# 12_-MCU_INPUTS.net
KiCad netlist of a schematic drawn in Altium Designer
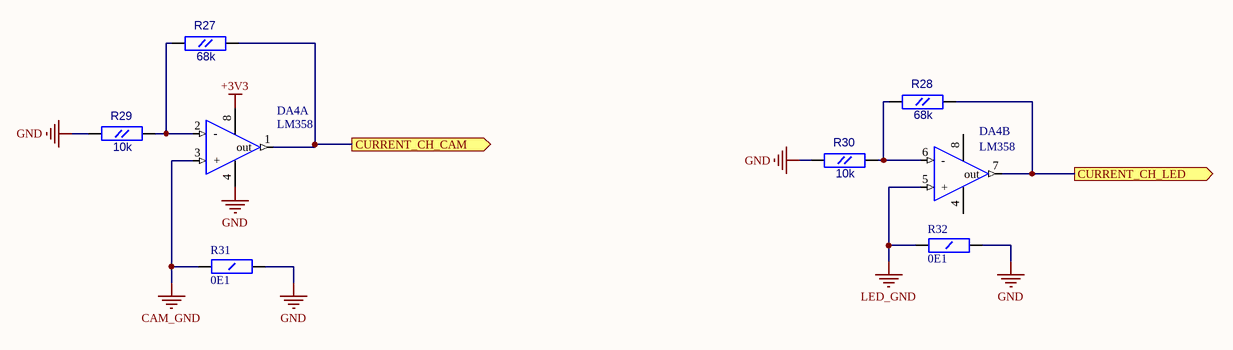
[diagram p0: [12]-MCU_INPUTS.SchDoc]

(export (version "E")
  (design (tool "Eeschema 10.0.6"))
  (components
    (comp (ref "DA4") (value "LM358") (footprint "SO-8") (libsource (lib "") (part "lm358_1")))
    (comp (ref "R27")
      (value "68k")
      (footprint "RC0603")
      (description "RC0603")
      (libsource (lib "fizik_lib") (part "RC0603"))
    )
    (comp (ref "R28")
      (value "68k")
      (footprint "RC0603")
      (description "RC0603")
      (libsource (lib "fizik_lib") (part "RC0603"))
    )
    (comp (ref "R29")
      (value "10k")
      (footprint "RC0603")
      (description "RC0603")
      (libsource (lib "fizik_lib") (part "RC0603"))
    )
    (comp (ref "R30")
      (value "10k")
      (footprint "RC0603")
      (description "RC0603")
      (libsource (lib "fizik_lib") (part "RC0603"))
    )
    (comp (ref "R31")
      (value "0E1")
      (footprint "R2512")
      (description "Resistor 2512 1W")
      (libsource (lib "fizik_lib") (part "RC2512"))
    )
    (comp (ref "R32")
      (value "0E1")
      (footprint "R2512")
      (description "Resistor 2512 1W")
      (libsource (lib "fizik_lib") (part "RC2512"))
    )
  )
  (nets
    (net (code "1") (name "+3V3") (class "Default")
      (node (ref "DA4") (pin "8") (pinfunction "V+_8") (pintype "passive"))
    )
    (net (code "2") (name "/CURRENT_CH_CAM") (class "Default")
      (node (ref "DA4") (pin "1") (pinfunction "out_1") (pintype "output"))
      (node (ref "R27") (pin "2") (pinfunction "B_2") (pintype "passive"))
    )
    (net (code "3") (name "/CURRENT_CH_LED") (class "Default")
      (node (ref "DA4") (pin "7") (pinfunction "out_7") (pintype "output"))
      (node (ref "R28") (pin "2") (pinfunction "B_2") (pintype "passive"))
    )
    (net (code "4") (name "CAM_GND") (class "Default")
      (node (ref "DA4") (pin "3") (pinfunction "+_3") (pintype "input"))
      (node (ref "R31") (pin "1") (pinfunction "A_1") (pintype "passive"))
    )
    (net (code "5") (name "GND") (class "Default")
      (node (ref "DA4") (pin "4") (pinfunction "V-_4") (pintype "passive"))
      (node (ref "R29") (pin "1") (pinfunction "A_1") (pintype "passive"))
      (node (ref "R30") (pin "1") (pinfunction "A_1") (pintype "passive"))
      (node (ref "R31") (pin "2") (pinfunction "B_2") (pintype "passive"))
      (node (ref "R32") (pin "2") (pinfunction "B_2") (pintype "passive"))
    )
    (net (code "6") (name "LED_GND") (class "Default")
      (node (ref "DA4") (pin "5") (pinfunction "+_5") (pintype "input"))
      (node (ref "R32") (pin "1") (pinfunction "A_1") (pintype "passive"))
    )
    (net (code "7") (name "Net-(DA4A--)") (class "Default")
      (node (ref "DA4") (pin "2") (pinfunction "-_2") (pintype "input"))
      (node (ref "R27") (pin "1") (pinfunction "A_1") (pintype "passive"))
      (node (ref "R29") (pin "2") (pinfunction "B_2") (pintype "passive"))
    )
    (net (code "8") (name "Net-(DA4B--)") (class "Default")
      (node (ref "DA4") (pin "6") (pinfunction "-_6") (pintype "input"))
      (node (ref "R28") (pin "1") (pinfunction "A_1") (pintype "passive"))
      (node (ref "R30") (pin "2") (pinfunction "B_2") (pintype "passive"))
    )
    (net (code "9") (name "unconnected-(DA4B-V+-Pad8)") (class "Default")
      (node (ref "DA4") (pin "8") (pinfunction "V+_8") (pintype "passive"))
    )
    (net (code "10") (name "unconnected-(DA4B-V--Pad4)") (class "Default")
      (node (ref "DA4") (pin "4") (pinfunction "V-_4") (pintype "passive"))
    )
  )
)
